# Power_Management.net
KiCad netlist of a schematic drawn in Altium Designer
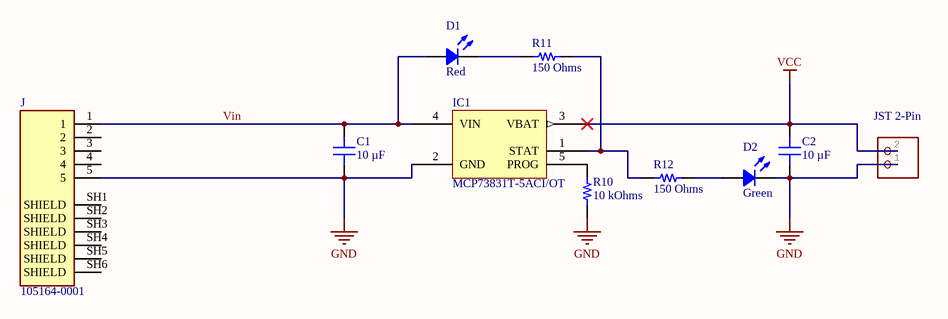
[diagram p0: Power_Management.SchDoc]

(export (version "E")
  (design (tool "Eeschema 10.0.6"))
  (components
    (comp (ref "C1")
      (value "10 µF")
      (footprint "CAP 0402_1005")
      (description "CAP CER 10UF 6.3V X5R 0402")
      (fields
        (field (name "PART NUMBER") "CL05A106MQ5NUNC")
        (field (name "MANUFACTURER") "Samsung Electro-Mechanics")
      )
      (libsource (lib "Celestial Altium Library - altium_library") (part "Capacitor"))
    )
    (comp (ref "C2")
      (value "10 µF")
      (footprint "CAP 0402_1005")
      (description "CAP CER 10UF 6.3V X5R 0402")
      (fields
        (field (name "PART NUMBER") "CL05A106MQ5NUNC")
        (field (name "MANUFACTURER") "Samsung Electro-Mechanics")
      )
      (libsource (lib "Celestial Altium Library - altium_library") (part "Capacitor"))
    )
    (comp (ref "CN1")
      (value "JSTPH")
      (footprint "PcbLib1:Lazy-JST")
      (description "JST 2-Pin Right-Angle Connector  PH-Series - 4UConnector: 17311  SH-Series - 4UConnector: 07278")
      (libsource (lib "microbuilder") (part "JST_2PIN"))
    )
    (comp (ref "D1")
      (value "Red")
      (footprint "LED 0402_1005 RED")
      (description "LED RED CLEAR CHIP SMD")
      (fields (field (name "PART NUMBER") "APHHS1005SURCK") (field (name "MANUFACTURER") "Kingbright"))
      (libsource (lib "Not Celestial Altium Library - altium_library") (part "LED"))
    )
    (comp (ref "D2")
      (value "Green")
      (footprint "LED 0402_1005 GREEN")
      (description "LED GREEN CLEAR CHIP SMD")
      (fields (field (name "PART NUMBER") "APHHS1005CGCK") (field (name "MANUFACTURER") "Kingbright"))
      (libsource (lib "Not Celestial Altium Library - altium_library") (part "LED"))
    )
    (comp (ref "IC1")
      (value "MCP73831T-5ACI/OT")
      (footprint "MICROCHIP SOT-23-5 OT")
      (description "IC CONTRLR LI-ION 4.50V SOT23-5")
      (libsource (lib "Celestial Altium Library - altium_library") (part "MICROCHIP MCP73831"))
    )
    (comp (ref "J")
      (value "105164-0001")
      (footprint "PcbLib1:MOLEX_105164-0001")
      (description "USB - micro B USB 2.0 Receptacle Connector 5 Position Surface Mount, Right Angle; Through Hole")
      (fields (field (name "MP") "1051640001") (field (name "MF") "Molex"))
      (libsource (lib "105164-0001") (part "105164-0001"))
    )
    (comp (ref "R10")
      (value "10 kOhms")
      (footprint "RES 0201_0603")
      (description "RES 10K OHM 1% 1/20W 0201")
      (fields (field (name "PART NUMBER") "RC0201FR-0710KL") (field (name "MANUFACTURER") "Yageo"))
      (libsource (lib "Celestial Altium Library - altium_library") (part "Resistor"))
    )
    (comp (ref "R11")
      (value "150 Ohms")
      (footprint "RES 0201_0603")
      (description "RES 150 OHM 1% 1/20W 0201")
      (fields (field (name "PART NUMBER") "RC0201FR-07150RL") (field (name "MANUFACTURER") "Yageo"))
      (libsource (lib "Celestial Altium Library - altium_library") (part "Resistor"))
    )
    (comp (ref "R12")
      (value "150 Ohms")
      (footprint "RES 0201_0603")
      (description "RES 150 OHM 1% 1/20W 0201")
      (fields (field (name "PART NUMBER") "RC0201FR-07150RL") (field (name "MANUFACTURER") "Yageo"))
      (libsource (lib "Celestial Altium Library - altium_library") (part "Resistor"))
    )
  )
  (nets
    (net (code "1") (name "/Vin") (class "Default")
      (node (ref "C1") (pin "2") (pinfunction "2_2") (pintype "passive"))
      (node (ref "D1") (pin "1") (pinfunction "1_1") (pintype "passive"))
      (node (ref "IC1") (pin "4") (pinfunction "VIN_4") (pintype "passive"))
      (node (ref "J") (pin "1") (pinfunction "1_1") (pintype "passive"))
    )
    (net (code "2") (name "GND") (class "Default")
      (node (ref "C1") (pin "1") (pinfunction "1_1") (pintype "passive"))
      (node (ref "C2") (pin "1") (pinfunction "1_1") (pintype "passive"))
      (node (ref "CN1") (pin "1") (pinfunction "1_1") (pintype "passive"))
      (node (ref "D2") (pin "2") (pinfunction "2_2") (pintype "passive"))
      (node (ref "IC1") (pin "2") (pinfunction "GND_2") (pintype "passive"))
      (node (ref "J") (pin "5") (pinfunction "5_5") (pintype "passive"))
      (node (ref "R10") (pin "1") (pinfunction "1_1") (pintype "passive"))
    )
    (net (code "3") (name "Net-(D1-Pad2)") (class "Default")
      (node (ref "D1") (pin "2") (pinfunction "2_2") (pintype "passive"))
      (node (ref "R11") (pin "1") (pinfunction "1_1") (pintype "passive"))
    )
    (net (code "4") (name "Net-(D2-Pad1)") (class "Default")
      (node (ref "D2") (pin "1") (pinfunction "1_1") (pintype "passive"))
      (node (ref "R12") (pin "2") (pinfunction "2_2") (pintype "passive"))
    )
    (net (code "5") (name "Net-(IC1-PROG)") (class "Default")
      (node (ref "IC1") (pin "5") (pinfunction "PROG_5") (pintype "passive"))
      (node (ref "R10") (pin "2") (pinfunction "2_2") (pintype "passive"))
    )
    (net (code "6") (name "Net-(IC1-STAT)") (class "Default")
      (node (ref "IC1") (pin "1") (pinfunction "STAT_1") (pintype "passive"))
      (node (ref "R11") (pin "2") (pinfunction "2_2") (pintype "passive"))
      (node (ref "R12") (pin "1") (pinfunction "1_1") (pintype "passive"))
    )
    (net (code "7") (name "VCC") (class "Default")
      (node (ref "C2") (pin "2") (pinfunction "2_2") (pintype "passive"))
      (node (ref "CN1") (pin "2") (pinfunction "2_2") (pintype "passive"))
      (node (ref "IC1") (pin "3") (pinfunction "VBAT_3") (pintype "output"))
    )
    (net (code "8") (name "unconnected-(J-Pad2)") (class "Default")
      (node (ref "J") (pin "2") (pinfunction "2_2") (pintype "passive"))
    )
    (net (code "9") (name "unconnected-(J-Pad3)") (class "Default")
      (node (ref "J") (pin "3") (pinfunction "3_3") (pintype "passive"))
    )
    (net (code "10") (name "unconnected-(J-Pad4)") (class "Default")
      (node (ref "J") (pin "4") (pinfunction "4_4") (pintype "passive"))
    )
    (net (code "11") (name "unconnected-(J-SHIELD-PadSH1)") (class "Default")
      (node (ref "J") (pin "SH1") (pinfunction "SHIELD_SH1") (pintype "passive"))
    )
    (net (code "12") (name "unconnected-(J-SHIELD-PadSH2)") (class "Default")
      (node (ref "J") (pin "SH2") (pinfunction "SHIELD_SH2") (pintype "passive"))
    )
    (net (code "13") (name "unconnected-(J-SHIELD-PadSH3)") (class "Default")
      (node (ref "J") (pin "SH3") (pinfunction "SHIELD_SH3") (pintype "passive"))
    )
    (net (code "14") (name "unconnected-(J-SHIELD-PadSH4)") (class "Default")
      (node (ref "J") (pin "SH4") (pinfunction "SHIELD_SH4") (pintype "passive"))
    )
    (net (code "15") (name "unconnected-(J-SHIELD-PadSH5)") (class "Default")
      (node (ref "J") (pin "SH5") (pinfunction "SHIELD_SH5") (pintype "passive"))
    )
    (net (code "16") (name "unconnected-(J-SHIELD-PadSH6)") (class "Default")
      (node (ref "J") (pin "SH6") (pinfunction "SHIELD_SH6") (pintype "passive"))
    )
  )
)
